# main.net
KiCad netlist of a schematic drawn in EAGLE
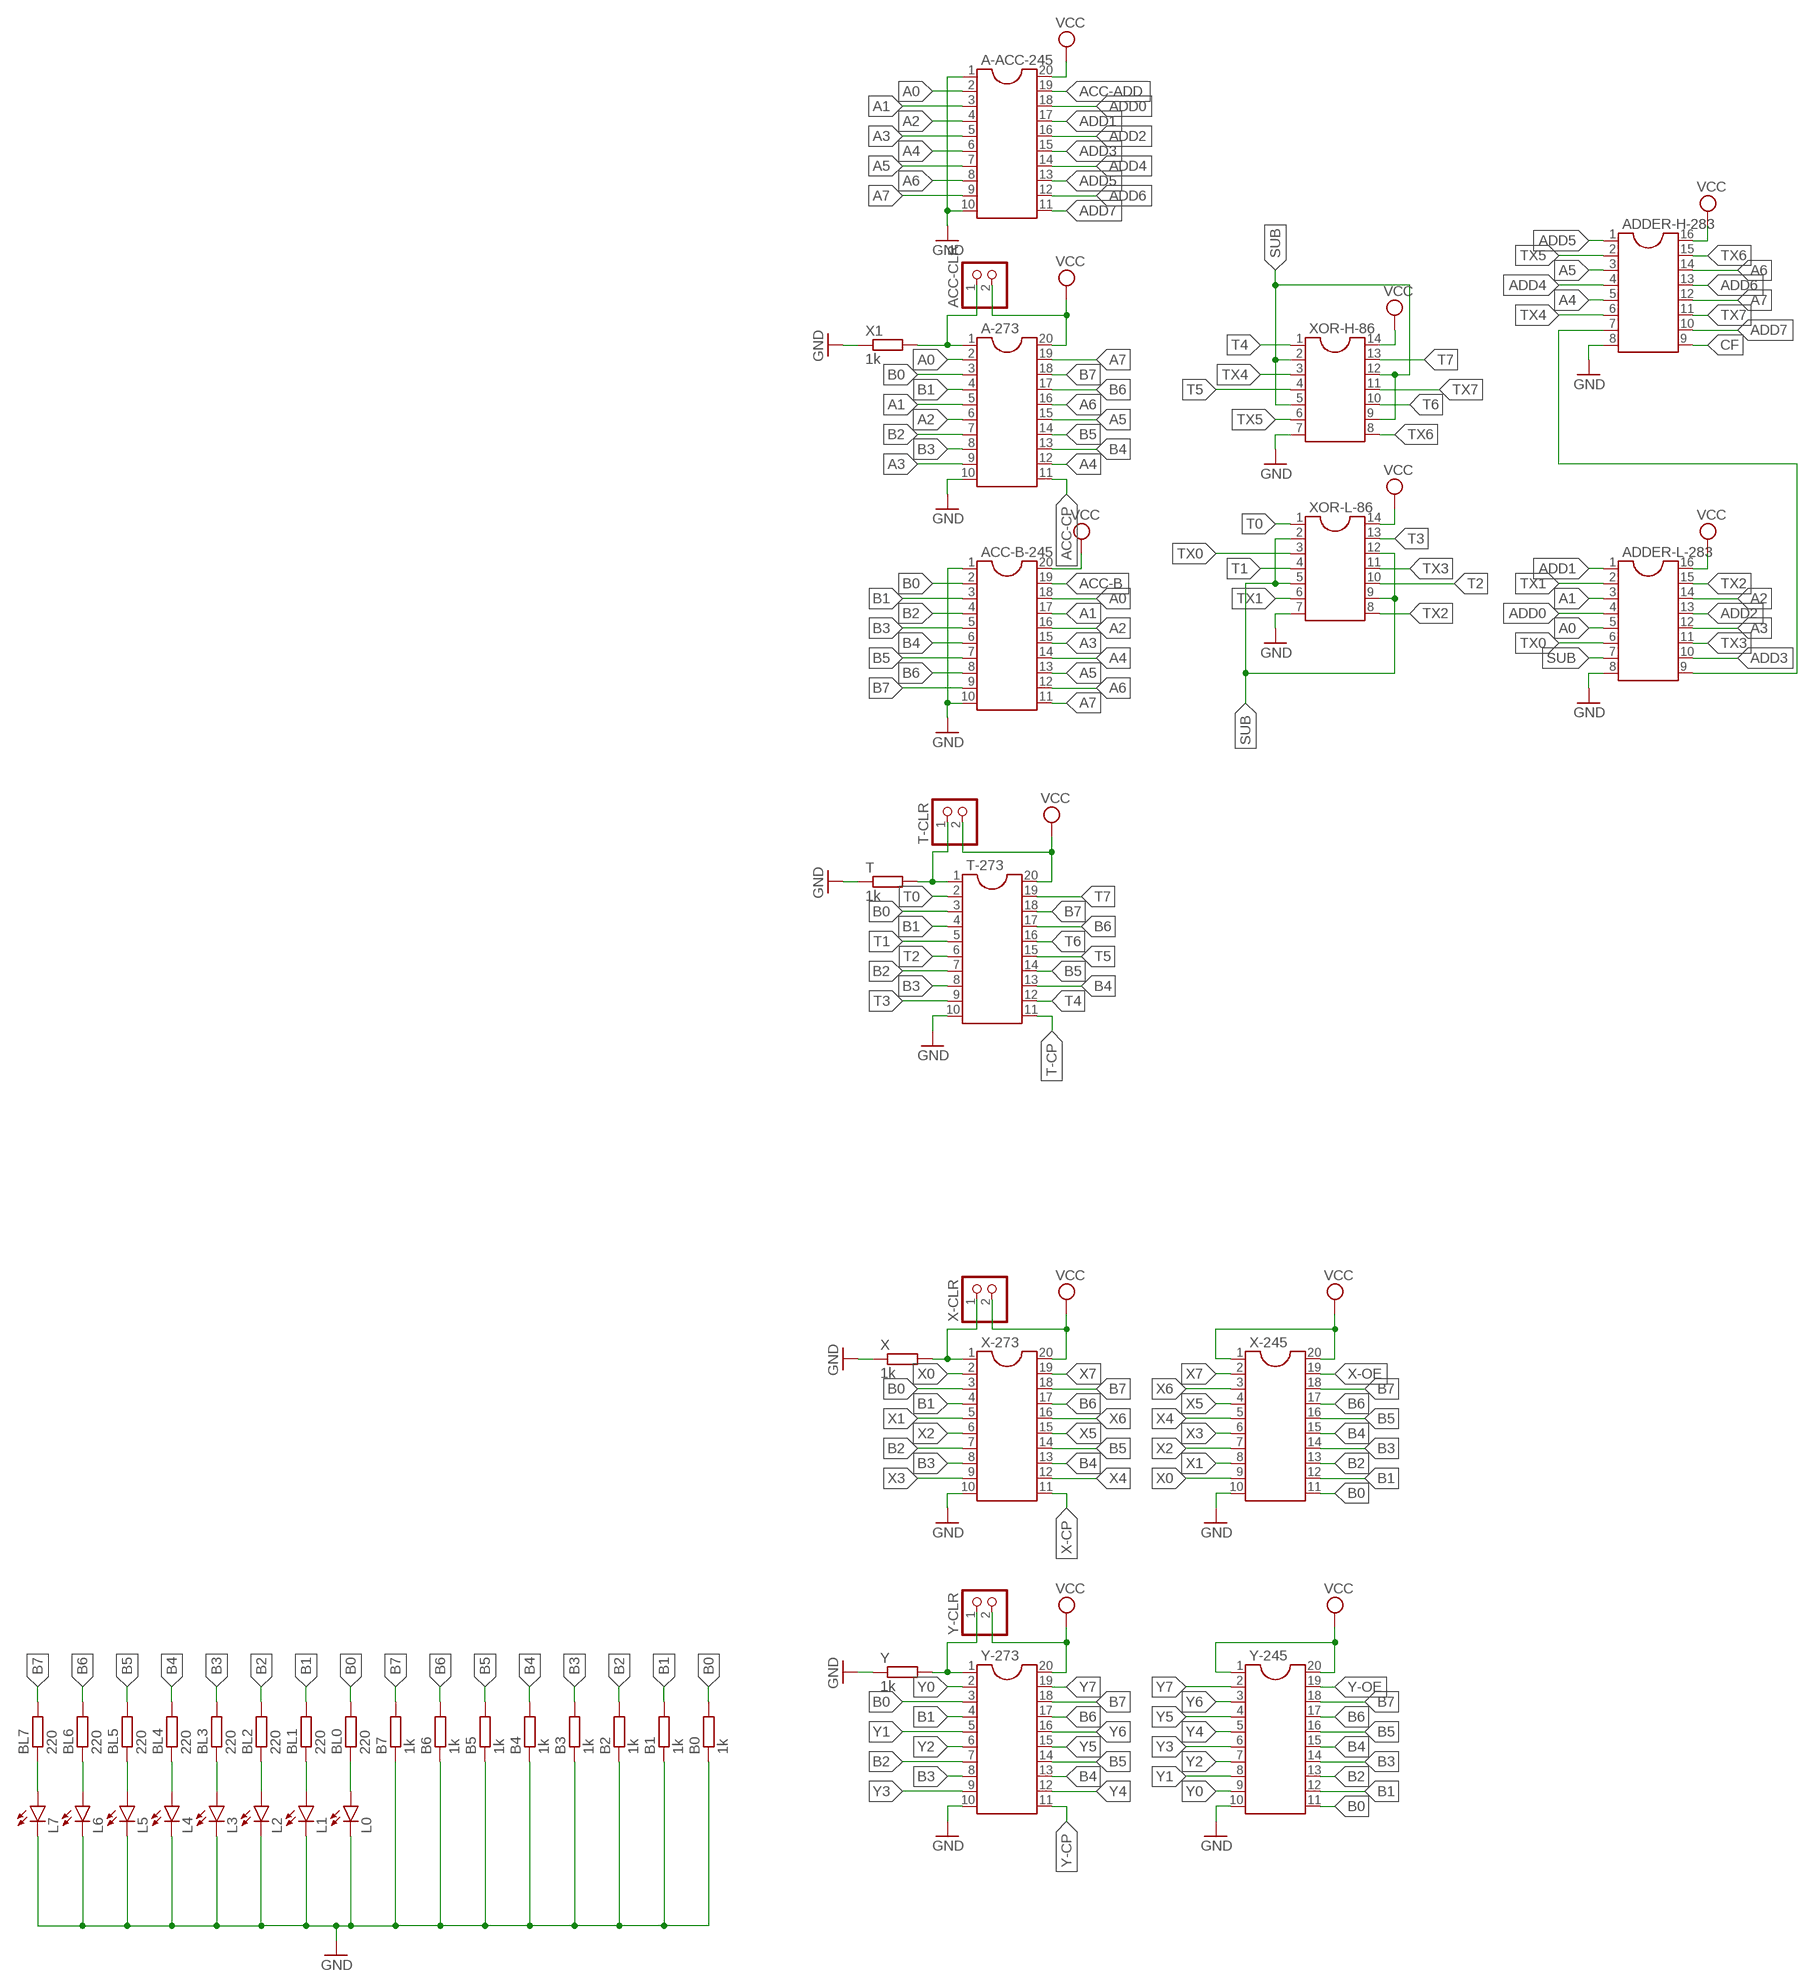
[diagram p0: schematic, sheet 1]

(export (version "E")
  (design (tool "Eeschema 10.0.6"))
  (components
    (comp (ref "A-273")
      (value "DIL20S")
      (footprint "eagle-import:SOCKET-20")
      (libsource (lib "eagle-import") (part "DIL20S"))
    )
    (comp (ref "A-ACC-245")
      (value "DIL20S")
      (footprint "eagle-import:SOCKET-20")
      (libsource (lib "eagle-import") (part "DIL20S"))
    )
    (comp (ref "ACC-B-245")
      (value "DIL20S")
      (footprint "eagle-import:SOCKET-20")
      (libsource (lib "eagle-import") (part "DIL20S"))
    )
    (comp (ref "ACC-CLR")
      (value "PINHD-1X2")
      (footprint "eagle-import:1X02")
      (libsource (lib "eagle-import") (part "PINHD-1X2"))
    )
    (comp (ref "ADDER-H-283")
      (value "DIL16S")
      (footprint "eagle-import:SOCKET-16")
      (libsource (lib "eagle-import") (part "DIL16S"))
    )
    (comp (ref "ADDER-L-283")
      (value "DIL16S")
      (footprint "eagle-import:SOCKET-16")
      (libsource (lib "eagle-import") (part "DIL16S"))
    )
    (comp (ref "B0")
      (value "1k")
      (footprint "eagle-import:0204_7")
      (libsource (lib "eagle-import") (part "R-EU_0204/7"))
    )
    (comp (ref "B1")
      (value "1k")
      (footprint "eagle-import:0204_7")
      (libsource (lib "eagle-import") (part "R-EU_0204/7"))
    )
    (comp (ref "B2")
      (value "1k")
      (footprint "eagle-import:0204_7")
      (libsource (lib "eagle-import") (part "R-EU_0204/7"))
    )
    (comp (ref "B3")
      (value "1k")
      (footprint "eagle-import:0204_7")
      (libsource (lib "eagle-import") (part "R-EU_0204/7"))
    )
    (comp (ref "B4")
      (value "1k")
      (footprint "eagle-import:0204_7")
      (libsource (lib "eagle-import") (part "R-EU_0204/7"))
    )
    (comp (ref "B5")
      (value "1k")
      (footprint "eagle-import:0204_7")
      (libsource (lib "eagle-import") (part "R-EU_0204/7"))
    )
    (comp (ref "B6")
      (value "1k")
      (footprint "eagle-import:0204_7")
      (libsource (lib "eagle-import") (part "R-EU_0204/7"))
    )
    (comp (ref "B7")
      (value "1k")
      (footprint "eagle-import:0204_7")
      (libsource (lib "eagle-import") (part "R-EU_0204/7"))
    )
    (comp (ref "BL0")
      (value "220")
      (footprint "eagle-import:0204_7")
      (libsource (lib "eagle-import") (part "R-EU_0204/7"))
    )
    (comp (ref "BL1")
      (value "220")
      (footprint "eagle-import:0204_7")
      (libsource (lib "eagle-import") (part "R-EU_0204/7"))
    )
    (comp (ref "BL2")
      (value "220")
      (footprint "eagle-import:0204_7")
      (libsource (lib "eagle-import") (part "R-EU_0204/7"))
    )
    (comp (ref "BL3")
      (value "220")
      (footprint "eagle-import:0204_7")
      (libsource (lib "eagle-import") (part "R-EU_0204/7"))
    )
    (comp (ref "BL4")
      (value "220")
      (footprint "eagle-import:0204_7")
      (libsource (lib "eagle-import") (part "R-EU_0204/7"))
    )
    (comp (ref "BL5")
      (value "220")
      (footprint "eagle-import:0204_7")
      (libsource (lib "eagle-import") (part "R-EU_0204/7"))
    )
    (comp (ref "BL6")
      (value "220")
      (footprint "eagle-import:0204_7")
      (libsource (lib "eagle-import") (part "R-EU_0204/7"))
    )
    (comp (ref "BL7")
      (value "220")
      (footprint "eagle-import:0204_7")
      (libsource (lib "eagle-import") (part "R-EU_0204/7"))
    )
    (comp (ref "L0")
      (value "LED5MM")
      (footprint "eagle-import:LED5MM")
      (libsource (lib "eagle-import") (part "LED5MM"))
    )
    (comp (ref "L1")
      (value "LED5MM")
      (footprint "eagle-import:LED5MM")
      (libsource (lib "eagle-import") (part "LED5MM"))
    )
    (comp (ref "L2")
      (value "LED5MM")
      (footprint "eagle-import:LED5MM")
      (libsource (lib "eagle-import") (part "LED5MM"))
    )
    (comp (ref "L3")
      (value "LED5MM")
      (footprint "eagle-import:LED5MM")
      (libsource (lib "eagle-import") (part "LED5MM"))
    )
    (comp (ref "L4")
      (value "LED5MM")
      (footprint "eagle-import:LED5MM")
      (libsource (lib "eagle-import") (part "LED5MM"))
    )
    (comp (ref "L5")
      (value "LED5MM")
      (footprint "eagle-import:LED5MM")
      (libsource (lib "eagle-import") (part "LED5MM"))
    )
    (comp (ref "L6")
      (value "LED5MM")
      (footprint "eagle-import:LED5MM")
      (libsource (lib "eagle-import") (part "LED5MM"))
    )
    (comp (ref "L7")
      (value "LED5MM")
      (footprint "eagle-import:LED5MM")
      (libsource (lib "eagle-import") (part "LED5MM"))
    )
    (comp (ref "T")
      (value "1k")
      (footprint "eagle-import:0204_7")
      (libsource (lib "eagle-import") (part "R-EU_0204/7"))
    )
    (comp (ref "T-273")
      (value "DIL20S")
      (footprint "eagle-import:SOCKET-20")
      (libsource (lib "eagle-import") (part "DIL20S"))
    )
    (comp (ref "T-CLR")
      (value "PINHD-1X2")
      (footprint "eagle-import:1X02")
      (libsource (lib "eagle-import") (part "PINHD-1X2"))
    )
    (comp (ref "X")
      (value "1k")
      (footprint "eagle-import:0204_7")
      (libsource (lib "eagle-import") (part "R-EU_0204/7"))
    )
    (comp (ref "X-245")
      (value "DIL20S")
      (footprint "eagle-import:SOCKET-20")
      (libsource (lib "eagle-import") (part "DIL20S"))
    )
    (comp (ref "X-273")
      (value "DIL20S")
      (footprint "eagle-import:SOCKET-20")
      (libsource (lib "eagle-import") (part "DIL20S"))
    )
    (comp (ref "X-CLR")
      (value "PINHD-1X2")
      (footprint "eagle-import:1X02")
      (libsource (lib "eagle-import") (part "PINHD-1X2"))
    )
    (comp (ref "X1")
      (value "1k")
      (footprint "eagle-import:0204_7")
      (libsource (lib "eagle-import") (part "R-EU_0204/7"))
    )
    (comp (ref "XOR-H-86")
      (value "DIL14S")
      (footprint "eagle-import:SOCKET-14")
      (libsource (lib "eagle-import") (part "DIL14S"))
    )
    (comp (ref "XOR-L-86")
      (value "DIL14S")
      (footprint "eagle-import:SOCKET-14")
      (libsource (lib "eagle-import") (part "DIL14S"))
    )
    (comp (ref "Y")
      (value "1k")
      (footprint "eagle-import:0204_7")
      (libsource (lib "eagle-import") (part "R-EU_0204/7"))
    )
    (comp (ref "Y-245")
      (value "DIL20S")
      (footprint "eagle-import:SOCKET-20")
      (libsource (lib "eagle-import") (part "DIL20S"))
    )
    (comp (ref "Y-273")
      (value "DIL20S")
      (footprint "eagle-import:SOCKET-20")
      (libsource (lib "eagle-import") (part "DIL20S"))
    )
    (comp (ref "Y-CLR")
      (value "PINHD-1X2")
      (footprint "eagle-import:1X02")
      (libsource (lib "eagle-import") (part "PINHD-1X2"))
    )
  )
  (nets
    (net (code "1") (name "A0") (class "Default")
      (node (ref "A-273") (pin "2") (pinfunction "2_2") (pintype "passive"))
      (node (ref "A-ACC-245") (pin "2") (pinfunction "2_2") (pintype "passive"))
      (node (ref "ACC-B-245") (pin "18") (pinfunction "18_18") (pintype "passive"))
      (node (ref "ADDER-L-283") (pin "5") (pinfunction "5_5") (pintype "passive"))
    )
    (net (code "2") (name "A1") (class "Default")
      (node (ref "A-273") (pin "5") (pinfunction "5_5") (pintype "passive"))
      (node (ref "A-ACC-245") (pin "3") (pinfunction "3_3") (pintype "passive"))
      (node (ref "ACC-B-245") (pin "17") (pinfunction "17_17") (pintype "passive"))
      (node (ref "ADDER-L-283") (pin "3") (pinfunction "3_3") (pintype "passive"))
    )
    (net (code "3") (name "A2") (class "Default")
      (node (ref "A-273") (pin "6") (pinfunction "6_6") (pintype "passive"))
      (node (ref "A-ACC-245") (pin "4") (pinfunction "4_4") (pintype "passive"))
      (node (ref "ACC-B-245") (pin "16") (pinfunction "16_16") (pintype "passive"))
      (node (ref "ADDER-L-283") (pin "14") (pinfunction "14_14") (pintype "passive"))
    )
    (net (code "4") (name "A3") (class "Default")
      (node (ref "A-273") (pin "9") (pinfunction "9_9") (pintype "passive"))
      (node (ref "A-ACC-245") (pin "5") (pinfunction "5_5") (pintype "passive"))
      (node (ref "ACC-B-245") (pin "15") (pinfunction "15_15") (pintype "passive"))
      (node (ref "ADDER-L-283") (pin "12") (pinfunction "12_12") (pintype "passive"))
    )
    (net (code "5") (name "A4") (class "Default")
      (node (ref "A-273") (pin "12") (pinfunction "12_12") (pintype "passive"))
      (node (ref "A-ACC-245") (pin "6") (pinfunction "6_6") (pintype "passive"))
      (node (ref "ACC-B-245") (pin "14") (pinfunction "14_14") (pintype "passive"))
      (node (ref "ADDER-H-283") (pin "5") (pinfunction "5_5") (pintype "passive"))
    )
    (net (code "6") (name "A5") (class "Default")
      (node (ref "A-273") (pin "15") (pinfunction "15_15") (pintype "passive"))
      (node (ref "A-ACC-245") (pin "7") (pinfunction "7_7") (pintype "passive"))
      (node (ref "ACC-B-245") (pin "13") (pinfunction "13_13") (pintype "passive"))
      (node (ref "ADDER-H-283") (pin "3") (pinfunction "3_3") (pintype "passive"))
    )
    (net (code "7") (name "A6") (class "Default")
      (node (ref "A-273") (pin "16") (pinfunction "16_16") (pintype "passive"))
      (node (ref "A-ACC-245") (pin "8") (pinfunction "8_8") (pintype "passive"))
      (node (ref "ACC-B-245") (pin "12") (pinfunction "12_12") (pintype "passive"))
      (node (ref "ADDER-H-283") (pin "14") (pinfunction "14_14") (pintype "passive"))
    )
    (net (code "8") (name "A7") (class "Default")
      (node (ref "A-273") (pin "19") (pinfunction "19_19") (pintype "passive"))
      (node (ref "A-ACC-245") (pin "9") (pinfunction "9_9") (pintype "passive"))
      (node (ref "ACC-B-245") (pin "11") (pinfunction "11_11") (pintype "passive"))
      (node (ref "ADDER-H-283") (pin "12") (pinfunction "12_12") (pintype "passive"))
    )
    (net (code "9") (name "ACC-ADD") (class "Default")
      (node (ref "A-ACC-245") (pin "19") (pinfunction "19_19") (pintype "passive"))
    )
    (net (code "10") (name "ACC-B") (class "Default")
      (node (ref "ACC-B-245") (pin "19") (pinfunction "19_19") (pintype "passive"))
    )
    (net (code "11") (name "ACC-CP") (class "Default")
      (node (ref "A-273") (pin "11") (pinfunction "11_11") (pintype "passive"))
    )
    (net (code "12") (name "ADD0") (class "Default")
      (node (ref "A-ACC-245") (pin "18") (pinfunction "18_18") (pintype "passive"))
      (node (ref "ADDER-L-283") (pin "4") (pinfunction "4_4") (pintype "passive"))
    )
    (net (code "13") (name "ADD1") (class "Default")
      (node (ref "A-ACC-245") (pin "17") (pinfunction "17_17") (pintype "passive"))
      (node (ref "ADDER-L-283") (pin "1") (pinfunction "1_1") (pintype "passive"))
    )
    (net (code "14") (name "ADD2") (class "Default")
      (node (ref "A-ACC-245") (pin "16") (pinfunction "16_16") (pintype "passive"))
      (node (ref "ADDER-L-283") (pin "13") (pinfunction "13_13") (pintype "passive"))
    )
    (net (code "15") (name "ADD3") (class "Default")
      (node (ref "A-ACC-245") (pin "15") (pinfunction "15_15") (pintype "passive"))
      (node (ref "ADDER-L-283") (pin "10") (pinfunction "10_10") (pintype "passive"))
    )
    (net (code "16") (name "ADD4") (class "Default")
      (node (ref "A-ACC-245") (pin "14") (pinfunction "14_14") (pintype "passive"))
      (node (ref "ADDER-H-283") (pin "4") (pinfunction "4_4") (pintype "passive"))
    )
    (net (code "17") (name "ADD5") (class "Default")
      (node (ref "A-ACC-245") (pin "13") (pinfunction "13_13") (pintype "passive"))
      (node (ref "ADDER-H-283") (pin "1") (pinfunction "1_1") (pintype "passive"))
    )
    (net (code "18") (name "ADD6") (class "Default")
      (node (ref "A-ACC-245") (pin "12") (pinfunction "12_12") (pintype "passive"))
      (node (ref "ADDER-H-283") (pin "13") (pinfunction "13_13") (pintype "passive"))
    )
    (net (code "19") (name "ADD7") (class "Default")
      (node (ref "A-ACC-245") (pin "11") (pinfunction "11_11") (pintype "passive"))
      (node (ref "ADDER-H-283") (pin "10") (pinfunction "10_10") (pintype "passive"))
    )
    (net (code "20") (name "B0") (class "Default")
      (node (ref "A-273") (pin "3") (pinfunction "3_3") (pintype "passive"))
      (node (ref "ACC-B-245") (pin "2") (pinfunction "2_2") (pintype "passive"))
      (node (ref "B0") (pin "2") (pinfunction "2_2") (pintype "passive"))
      (node (ref "BL0") (pin "2") (pinfunction "2_2") (pintype "passive"))
      (node (ref "T-273") (pin "3") (pinfunction "3_3") (pintype "passive"))
      (node (ref "X-245") (pin "11") (pinfunction "11_11") (pintype "passive"))
      (node (ref "X-273") (pin "3") (pinfunction "3_3") (pintype "passive"))
      (node (ref "Y-245") (pin "11") (pinfunction "11_11") (pintype "passive"))
      (node (ref "Y-273") (pin "3") (pinfunction "3_3") (pintype "passive"))
    )
    (net (code "21") (name "B1") (class "Default")
      (node (ref "A-273") (pin "4") (pinfunction "4_4") (pintype "passive"))
      (node (ref "ACC-B-245") (pin "3") (pinfunction "3_3") (pintype "passive"))
      (node (ref "B1") (pin "2") (pinfunction "2_2") (pintype "passive"))
      (node (ref "BL1") (pin "2") (pinfunction "2_2") (pintype "passive"))
      (node (ref "T-273") (pin "4") (pinfunction "4_4") (pintype "passive"))
      (node (ref "X-245") (pin "12") (pinfunction "12_12") (pintype "passive"))
      (node (ref "X-273") (pin "4") (pinfunction "4_4") (pintype "passive"))
      (node (ref "Y-245") (pin "12") (pinfunction "12_12") (pintype "passive"))
      (node (ref "Y-273") (pin "4") (pinfunction "4_4") (pintype "passive"))
    )
    (net (code "22") (name "B2") (class "Default")
      (node (ref "A-273") (pin "7") (pinfunction "7_7") (pintype "passive"))
      (node (ref "ACC-B-245") (pin "4") (pinfunction "4_4") (pintype "passive"))
      (node (ref "B2") (pin "2") (pinfunction "2_2") (pintype "passive"))
      (node (ref "BL2") (pin "2") (pinfunction "2_2") (pintype "passive"))
      (node (ref "T-273") (pin "7") (pinfunction "7_7") (pintype "passive"))
      (node (ref "X-245") (pin "13") (pinfunction "13_13") (pintype "passive"))
      (node (ref "X-273") (pin "7") (pinfunction "7_7") (pintype "passive"))
      (node (ref "Y-245") (pin "13") (pinfunction "13_13") (pintype "passive"))
      (node (ref "Y-273") (pin "7") (pinfunction "7_7") (pintype "passive"))
    )
    (net (code "23") (name "B3") (class "Default")
      (node (ref "A-273") (pin "8") (pinfunction "8_8") (pintype "passive"))
      (node (ref "ACC-B-245") (pin "5") (pinfunction "5_5") (pintype "passive"))
      (node (ref "B3") (pin "2") (pinfunction "2_2") (pintype "passive"))
      (node (ref "BL3") (pin "2") (pinfunction "2_2") (pintype "passive"))
      (node (ref "T-273") (pin "8") (pinfunction "8_8") (pintype "passive"))
      (node (ref "X-245") (pin "14") (pinfunction "14_14") (pintype "passive"))
      (node (ref "X-273") (pin "8") (pinfunction "8_8") (pintype "passive"))
      (node (ref "Y-245") (pin "14") (pinfunction "14_14") (pintype "passive"))
      (node (ref "Y-273") (pin "8") (pinfunction "8_8") (pintype "passive"))
    )
    (net (code "24") (name "B4") (class "Default")
      (node (ref "A-273") (pin "13") (pinfunction "13_13") (pintype "passive"))
      (node (ref "ACC-B-245") (pin "6") (pinfunction "6_6") (pintype "passive"))
      (node (ref "B4") (pin "2") (pinfunction "2_2") (pintype "passive"))
      (node (ref "BL4") (pin "2") (pinfunction "2_2") (pintype "passive"))
      (node (ref "T-273") (pin "13") (pinfunction "13_13") (pintype "passive"))
      (node (ref "X-245") (pin "15") (pinfunction "15_15") (pintype "passive"))
      (node (ref "X-273") (pin "13") (pinfunction "13_13") (pintype "passive"))
      (node (ref "Y-245") (pin "15") (pinfunction "15_15") (pintype "passive"))
      (node (ref "Y-273") (pin "13") (pinfunction "13_13") (pintype "passive"))
    )
    (net (code "25") (name "B5") (class "Default")
      (node (ref "A-273") (pin "14") (pinfunction "14_14") (pintype "passive"))
      (node (ref "ACC-B-245") (pin "7") (pinfunction "7_7") (pintype "passive"))
      (node (ref "B5") (pin "2") (pinfunction "2_2") (pintype "passive"))
      (node (ref "BL5") (pin "2") (pinfunction "2_2") (pintype "passive"))
      (node (ref "T-273") (pin "14") (pinfunction "14_14") (pintype "passive"))
      (node (ref "X-245") (pin "16") (pinfunction "16_16") (pintype "passive"))
      (node (ref "X-273") (pin "14") (pinfunction "14_14") (pintype "passive"))
      (node (ref "Y-245") (pin "16") (pinfunction "16_16") (pintype "passive"))
      (node (ref "Y-273") (pin "14") (pinfunction "14_14") (pintype "passive"))
    )
    (net (code "26") (name "B6") (class "Default")
      (node (ref "A-273") (pin "17") (pinfunction "17_17") (pintype "passive"))
      (node (ref "ACC-B-245") (pin "8") (pinfunction "8_8") (pintype "passive"))
      (node (ref "B6") (pin "2") (pinfunction "2_2") (pintype "passive"))
      (node (ref "BL6") (pin "2") (pinfunction "2_2") (pintype "passive"))
      (node (ref "T-273") (pin "17") (pinfunction "17_17") (pintype "passive"))
      (node (ref "X-245") (pin "17") (pinfunction "17_17") (pintype "passive"))
      (node (ref "X-273") (pin "17") (pinfunction "17_17") (pintype "passive"))
      (node (ref "Y-245") (pin "17") (pinfunction "17_17") (pintype "passive"))
      (node (ref "Y-273") (pin "17") (pinfunction "17_17") (pintype "passive"))
    )
    (net (code "27") (name "B7") (class "Default")
      (node (ref "A-273") (pin "18") (pinfunction "18_18") (pintype "passive"))
      (node (ref "ACC-B-245") (pin "9") (pinfunction "9_9") (pintype "passive"))
      (node (ref "B7") (pin "2") (pinfunction "2_2") (pintype "passive"))
      (node (ref "BL7") (pin "2") (pinfunction "2_2") (pintype "passive"))
      (node (ref "T-273") (pin "18") (pinfunction "18_18") (pintype "passive"))
      (node (ref "X-245") (pin "18") (pinfunction "18_18") (pintype "passive"))
      (node (ref "X-273") (pin "18") (pinfunction "18_18") (pintype "passive"))
      (node (ref "Y-245") (pin "18") (pinfunction "18_18") (pintype "passive"))
      (node (ref "Y-273") (pin "18") (pinfunction "18_18") (pintype "passive"))
    )
    (net (code "28") (name "CF") (class "Default")
      (node (ref "ADDER-H-283") (pin "9") (pinfunction "9_9") (pintype "passive"))
    )
    (net (code "29") (name "GND") (class "Default")
      (node (ref "A-273") (pin "10") (pinfunction "10_10") (pintype "passive"))
      (node (ref "A-ACC-245") (pin "1") (pinfunction "1_1") (pintype "passive"))
      (node (ref "A-ACC-245") (pin "10") (pinfunction "10_10") (pintype "passive"))
      (node (ref "ACC-B-245") (pin "1") (pinfunction "1_1") (pintype "passive"))
      (node (ref "ACC-B-245") (pin "10") (pinfunction "10_10") (pintype "passive"))
      (node (ref "ADDER-H-283") (pin "8") (pinfunction "8_8") (pintype "passive"))
      (node (ref "ADDER-L-283") (pin "8") (pinfunction "8_8") (pintype "passive"))
      (node (ref "B0") (pin "1") (pinfunction "1_1") (pintype "passive"))
      (node (ref "B1") (pin "1") (pinfunction "1_1") (pintype "passive"))
      (node (ref "B2") (pin "1") (pinfunction "1_1") (pintype "passive"))
      (node (ref "B3") (pin "1") (pinfunction "1_1") (pintype "passive"))
      (node (ref "B4") (pin "1") (pinfunction "1_1") (pintype "passive"))
      (node (ref "B5") (pin "1") (pinfunction "1_1") (pintype "passive"))
      (node (ref "B6") (pin "1") (pinfunction "1_1") (pintype "passive"))
      (node (ref "B7") (pin "1") (pinfunction "1_1") (pintype "passive"))
      (node (ref "L0") (pin "K") (pinfunction "C_K") (pintype "passive"))
      (node (ref "L1") (pin "K") (pinfunction "C_K") (pintype "passive"))
      (node (ref "L2") (pin "K") (pinfunction "C_K") (pintype "passive"))
      (node (ref "L3") (pin "K") (pinfunction "C_K") (pintype "passive"))
      (node (ref "L4") (pin "K") (pinfunction "C_K") (pintype "passive"))
      (node (ref "L5") (pin "K") (pinfunction "C_K") (pintype "passive"))
      (node (ref "L6") (pin "K") (pinfunction "C_K") (pintype "passive"))
      (node (ref "L7") (pin "K") (pinfunction "C_K") (pintype "passive"))
      (node (ref "T") (pin "1") (pinfunction "1_1") (pintype "passive"))
      (node (ref "T-273") (pin "10") (pinfunction "10_10") (pintype "passive"))
      (node (ref "X") (pin "1") (pinfunction "1_1") (pintype "passive"))
      (node (ref "X-245") (pin "10") (pinfunction "10_10") (pintype "passive"))
      (node (ref "X-273") (pin "10") (pinfunction "10_10") (pintype "passive"))
      (node (ref "X1") (pin "1") (pinfunction "1_1") (pintype "passive"))
      (node (ref "XOR-H-86") (pin "7") (pinfunction "7_7") (pintype "passive"))
      (node (ref "XOR-L-86") (pin "7") (pinfunction "7_7") (pintype "passive"))
      (node (ref "Y") (pin "1") (pinfunction "1_1") (pintype "passive"))
      (node (ref "Y-245") (pin "10") (pinfunction "10_10") (pintype "passive"))
      (node (ref "Y-273") (pin "10") (pinfunction "10_10") (pintype "passive"))
    )
    (net (code "30") (name "Net-(A-273-Pad1)") (class "Default")
      (node (ref "A-273") (pin "1") (pinfunction "1_1") (pintype "passive"))
      (node (ref "ACC-CLR") (pin "1") (pinfunction "1_1") (pintype "passive"))
      (node (ref "X1") (pin "2") (pinfunction "2_2") (pintype "passive"))
    )
    (net (code "31") (name "Net-(ADDER-H-283-Pad7)") (class "Default")
      (node (ref "ADDER-H-283") (pin "7") (pinfunction "7_7") (pintype "passive"))
      (node (ref "ADDER-L-283") (pin "9") (pinfunction "9_9") (pintype "passive"))
    )
    (net (code "32") (name "Net-(BL0-Pad1)") (class "Default")
      (node (ref "BL0") (pin "1") (pinfunction "1_1") (pintype "passive"))
      (node (ref "L0") (pin "A") (pinfunction "A_A") (pintype "passive"))
    )
    (net (code "33") (name "Net-(BL1-Pad1)") (class "Default")
      (node (ref "BL1") (pin "1") (pinfunction "1_1") (pintype "passive"))
      (node (ref "L1") (pin "A") (pinfunction "A_A") (pintype "passive"))
    )
    (net (code "34") (name "Net-(BL2-Pad1)") (class "Default")
      (node (ref "BL2") (pin "1") (pinfunction "1_1") (pintype "passive"))
      (node (ref "L2") (pin "A") (pinfunction "A_A") (pintype "passive"))
    )
    (net (code "35") (name "Net-(BL3-Pad1)") (class "Default")
      (node (ref "BL3") (pin "1") (pinfunction "1_1") (pintype "passive"))
      (node (ref "L3") (pin "A") (pinfunction "A_A") (pintype "passive"))
    )
    (net (code "36") (name "Net-(BL4-Pad1)") (class "Default")
      (node (ref "BL4") (pin "1") (pinfunction "1_1") (pintype "passive"))
      (node (ref "L4") (pin "A") (pinfunction "A_A") (pintype "passive"))
    )
    (net (code "37") (name "Net-(BL5-Pad1)") (class "Default")
      (node (ref "BL5") (pin "1") (pinfunction "1_1") (pintype "passive"))
      (node (ref "L5") (pin "A") (pinfunction "A_A") (pintype "passive"))
    )
    (net (code "38") (name "Net-(BL6-Pad1)") (class "Default")
      (node (ref "BL6") (pin "1") (pinfunction "1_1") (pintype "passive"))
      (node (ref "L6") (pin "A") (pinfunction "A_A") (pintype "passive"))
    )
    (net (code "39") (name "Net-(BL7-Pad1)") (class "Default")
      (node (ref "BL7") (pin "1") (pinfunction "1_1") (pintype "passive"))
      (node (ref "L7") (pin "A") (pinfunction "A_A") (pintype "passive"))
    )
    (net (code "40") (name "Net-(T-273-Pad1)") (class "Default")
      (node (ref "T") (pin "2") (pinfunction "2_2") (pintype "passive"))
      (node (ref "T-273") (pin "1") (pinfunction "1_1") (pintype "passive"))
      (node (ref "T-CLR") (pin "1") (pinfunction "1_1") (pintype "passive"))
    )
    (net (code "41") (name "Net-(X-273-Pad1)") (class "Default")
      (node (ref "X") (pin "2") (pinfunction "2_2") (pintype "passive"))
      (node (ref "X-273") (pin "1") (pinfunction "1_1") (pintype "passive"))
      (node (ref "X-CLR") (pin "1") (pinfunction "1_1") (pintype "passive"))
    )
    (net (code "42") (name "Net-(Y-273-Pad1)") (class "Default")
      (node (ref "Y") (pin "2") (pinfunction "2_2") (pintype "passive"))
      (node (ref "Y-273") (pin "1") (pinfunction "1_1") (pintype "passive"))
      (node (ref "Y-CLR") (pin "1") (pinfunction "1_1") (pintype "passive"))
    )
    (net (code "43") (name "SUB") (class "Default")
      (node (ref "ADDER-L-283") (pin "7") (pinfunction "7_7") (pintype "passive"))
      (node (ref "XOR-H-86") (pin "12") (pinfunction "12_12") (pintype "passive"))
      (node (ref "XOR-H-86") (pin "2") (pinfunction "2_2") (pintype "passive"))
      (node (ref "XOR-H-86") (pin "5") (pinfunction "5_5") (pintype "passive"))
      (node (ref "XOR-H-86") (pin "9") (pinfunction "9_9") (pintype "passive"))
      (node (ref "XOR-L-86") (pin "12") (pinfunction "12_12") (pintype "passive"))
      (node (ref "XOR-L-86") (pin "2") (pinfunction "2_2") (pintype "passive"))
      (node (ref "XOR-L-86") (pin "5") (pinfunction "5_5") (pintype "passive"))
      (node (ref "XOR-L-86") (pin "9") (pinfunction "9_9") (pintype "passive"))
    )
    (net (code "44") (name "T-CP") (class "Default")
      (node (ref "T-273") (pin "11") (pinfunction "11_11") (pintype "passive"))
    )
    (net (code "45") (name "T0") (class "Default")
      (node (ref "T-273") (pin "2") (pinfunction "2_2") (pintype "passive"))
      (node (ref "XOR-L-86") (pin "1") (pinfunction "1_1") (pintype "passive"))
    )
    (net (code "46") (name "T1") (class "Default")
      (node (ref "T-273") (pin "5") (pinfunction "5_5") (pintype "passive"))
      (node (ref "XOR-L-86") (pin "4") (pinfunction "4_4") (pintype "passive"))
    )
    (net (code "47") (name "T2") (class "Default")
      (node (ref "T-273") (pin "6") (pinfunction "6_6") (pintype "passive"))
      (node (ref "XOR-L-86") (pin "10") (pinfunction "10_10") (pintype "passive"))
    )
    (net (code "48") (name "T3") (class "Default")
      (node (ref "T-273") (pin "9") (pinfunction "9_9") (pintype "passive"))
      (node (ref "XOR-L-86") (pin "13") (pinfunction "13_13") (pintype "passive"))
    )
    (net (code "49") (name "T4") (class "Default")
      (node (ref "T-273") (pin "12") (pinfunction "12_12") (pintype "passive"))
      (node (ref "XOR-H-86") (pin "1") (pinfunction "1_1") (pintype "passive"))
    )
    (net (code "50") (name "T5") (class "Default")
      (node (ref "T-273") (pin "15") (pinfunction "15_15") (pintype "passive"))
      (node (ref "XOR-H-86") (pin "4") (pinfunction "4_4") (pintype "passive"))
    )
    (net (code "51") (name "T6") (class "Default")
      (node (ref "T-273") (pin "16") (pinfunction "16_16") (pintype "passive"))
      (node (ref "XOR-H-86") (pin "10") (pinfunction "10_10") (pintype "passive"))
    )
    (net (code "52") (name "T7") (class "Default")
      (node (ref "T-273") (pin "19") (pinfunction "19_19") (pintype "passive"))
      (node (ref "XOR-H-86") (pin "13") (pinfunction "13_13") (pintype "passive"))
    )
    (net (code "53") (name "TX0") (class "Default")
      (node (ref "ADDER-L-283") (pin "6") (pinfunction "6_6") (pintype "passive"))
      (node (ref "XOR-L-86") (pin "3") (pinfunction "3_3") (pintype "passive"))
    )
    (net (code "54") (name "TX1") (class "Default")
      (node (ref "ADDER-L-283") (pin "2") (pinfunction "2_2") (pintype "passive"))
      (node (ref "XOR-L-86") (pin "6") (pinfunction "6_6") (pintype "passive"))
    )
    (net (code "55") (name "TX2") (class "Default")
      (node (ref "ADDER-L-283") (pin "15") (pinfunction "15_15") (pintype "passive"))
      (node (ref "XOR-L-86") (pin "8") (pinfunction "8_8") (pintype "passive"))
    )
    (net (code "56") (name "TX3") (class "Default")
      (node (ref "ADDER-L-283") (pin "11") (pinfunction "11_11") (pintype "passive"))
      (node (ref "XOR-L-86") (pin "11") (pinfunction "11_11") (pintype "passive"))
    )
    (net (code "57") (name "TX4") (class "Default")
      (node (ref "ADDER-H-283") (pin "6") (pinfunction "6_6") (pintype "passive"))
      (node (ref "XOR-H-86") (pin "3") (pinfunction "3_3") (pintype "passive"))
    )
    (net (code "58") (name "TX5") (class "Default")
      (node (ref "ADDER-H-283") (pin "2") (pinfunction "2_2") (pintype "passive"))
      (node (ref "XOR-H-86") (pin "6") (pinfunction "6_6") (pintype "passive"))
    )
    (net (code "59") (name "TX6") (class "Default")
      (node (ref "ADDER-H-283") (pin "15") (pinfunction "15_15") (pintype "passive"))
      (node (ref "XOR-H-86") (pin "8") (pinfunction "8_8") (pintype "passive"))
    )
    (net (code "60") (name "TX7") (class "Default")
      (node (ref "ADDER-H-283") (pin "11") (pinfunction "11_11") (pintype "passive"))
      (node (ref "XOR-H-86") (pin "11") (pinfunction "11_11") (pintype "passive"))
    )
    (net (code "61") (name "VCC") (class "Default")
      (node (ref "A-273") (pin "20") (pinfunction "20_20") (pintype "passive"))
      (node (ref "A-ACC-245") (pin "20") (pinfunction "20_20") (pintype "passive"))
      (node (ref "ACC-B-245") (pin "20") (pinfunction "20_20") (pintype "passive"))
      (node (ref "ACC-CLR") (pin "2") (pinfunction "2_2") (pintype "passive"))
      (node (ref "ADDER-H-283") (pin "16") (pinfunction "16_16") (pintype "passive"))
      (node (ref "ADDER-L-283") (pin "16") (pinfunction "16_16") (pintype "passive"))
      (node (ref "T-273") (pin "20") (pinfunction "20_20") (pintype "passive"))
      (node (ref "T-CLR") (pin "2") (pinfunction "2_2") (pintype "passive"))
      (node (ref "X-245") (pin "1") (pinfunction "1_1") (pintype "passive"))
      (node (ref "X-245") (pin "20") (pinfunction "20_20") (pintype "passive"))
      (node (ref "X-273") (pin "20") (pinfunction "20_20") (pintype "passive"))
      (node (ref "X-CLR") (pin "2") (pinfunction "2_2") (pintype "passive"))
      (node (ref "XOR-H-86") (pin "14") (pinfunction "14_14") (pintype "passive"))
      (node (ref "XOR-L-86") (pin "14") (pinfunction "14_14") (pintype "passive"))
      (node (ref "Y-245") (pin "1") (pinfunction "1_1") (pintype "passive"))
      (node (ref "Y-245") (pin "20") (pinfunction "20_20") (pintype "passive"))
      (node (ref "Y-273") (pin "20") (pinfunction "20_20") (pintype "passive"))
      (node (ref "Y-CLR") (pin "2") (pinfunction "2_2") (pintype "passive"))
    )
    (net (code "62") (name "X-CP") (class "Default")
      (node (ref "X-273") (pin "11") (pinfunction "11_11") (pintype "passive"))
    )
    (net (code "63") (name "X-OE") (class "Default")
      (node (ref "X-245") (pin "19") (pinfunction "19_19") (pintype "passive"))
    )
    (net (code "64") (name "X0") (class "Default")
      (node (ref "X-245") (pin "9") (pinfunction "9_9") (pintype "passive"))
      (node (ref "X-273") (pin "2") (pinfunction "2_2") (pintype "passive"))
    )
    (net (code "65") (name "X1") (class "Default")
      (node (ref "X-245") (pin "8") (pinfunction "8_8") (pintype "passive"))
      (node (ref "X-273") (pin "5") (pinfunction "5_5") (pintype "passive"))
    )
    (net (code "66") (name "X2") (class "Default")
      (node (ref "X-245") (pin "7") (pinfunction "7_7") (pintype "passive"))
      (node (ref "X-273") (pin "6") (pinfunction "6_6") (pintype "passive"))
    )
    (net (code "67") (name "X3") (class "Default")
      (node (ref "X-245") (pin "6") (pinfunction "6_6") (pintype "passive"))
      (node (ref "X-273") (pin "9") (pinfunction "9_9") (pintype "passive"))
    )
    (net (code "68") (name "X4") (class "Default")
      (node (ref "X-245") (pin "5") (pinfunction "5_5") (pintype "passive"))
      (node (ref "X-273") (pin "12") (pinfunction "12_12") (pintype "passive"))
    )
    (net (code "69") (name "X5") (class "Default")
      (node (ref "X-245") (pin "4") (pinfunction "4_4") (pintype "passive"))
      (node (ref "X-273") (pin "15") (pinfunction "15_15") (pintype "passive"))
    )
    (net (code "70") (name "X6") (class "Default")
      (node (ref "X-245") (pin "3") (pinfunction "3_3") (pintype "passive"))
      (node (ref "X-273") (pin "16") (pinfunction "16_16") (pintype "passive"))
    )
    (net (code "71") (name "X7") (class "Default")
      (node (ref "X-245") (pin "2") (pinfunction "2_2") (pintype "passive"))
      (node (ref "X-273") (pin "19") (pinfunction "19_19") (pintype "passive"))
    )
    (net (code "72") (name "Y-CP") (class "Default")
      (node (ref "Y-273") (pin "11") (pinfunction "11_11") (pintype "passive"))
    )
    (net (code "73") (name "Y-OE") (class "Default")
      (node (ref "Y-245") (pin "19") (pinfunction "19_19") (pintype "passive"))
    )
    (net (code "74") (name "Y0") (class "Default")
      (node (ref "Y-245") (pin "9") (pinfunction "9_9") (pintype "passive"))
      (node (ref "Y-273") (pin "2") (pinfunction "2_2") (pintype "passive"))
    )
    (net (code "75") (name "Y1") (class "Default")
      (node (ref "Y-245") (pin "8") (pinfunction "8_8") (pintype "passive"))
      (node (ref "Y-273") (pin "5") (pinfunction "5_5") (pintype "passive"))
    )
    (net (code "76") (name "Y2") (class "Default")
      (node (ref "Y-245") (pin "7") (pinfunction "7_7") (pintype "passive"))
      (node (ref "Y-273") (pin "6") (pinfunction "6_6") (pintype "passive"))
    )
    (net (code "77") (name "Y3") (class "Default")
      (node (ref "Y-245") (pin "6") (pinfunction "6_6") (pintype "passive"))
      (node (ref "Y-273") (pin "9") (pinfunction "9_9") (pintype "passive"))
    )
    (net (code "78") (name "Y4") (class "Default")
      (node (ref "Y-245") (pin "5") (pinfunction "5_5") (pintype "passive"))
      (node (ref "Y-273") (pin "12") (pinfunction "12_12") (pintype "passive"))
    )
    (net (code "79") (name "Y5") (class "Default")
      (node (ref "Y-245") (pin "4") (pinfunction "4_4") (pintype "passive"))
      (node (ref "Y-273") (pin "15") (pinfunction "15_15") (pintype "passive"))
    )
    (net (code "80") (name "Y6") (class "Default")
      (node (ref "Y-245") (pin "3") (pinfunction "3_3") (pintype "passive"))
      (node (ref "Y-273") (pin "16") (pinfunction "16_16") (pintype "passive"))
    )
    (net (code "81") (name "Y7") (class "Default")
      (node (ref "Y-245") (pin "2") (pinfunction "2_2") (pintype "passive"))
      (node (ref "Y-273") (pin "19") (pinfunction "19_19") (pintype "passive"))
    )
  )
)
